# CircuitoEmitter2_0.net
KiCad netlist of a schematic drawn in EAGLE
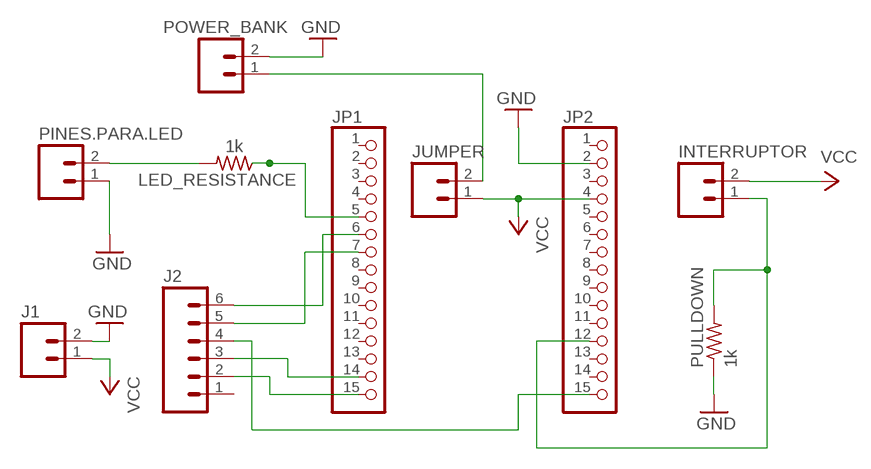
[diagram p0: schematic, sheet 1]

(export (version "E")
  (design (tool "Eeschema 10.0.6"))
  (components
    (comp (ref "INTERRUPTOR")
      (value "M02LOCK_LONGPADS")
      (footprint "eagle-import:1X02_LOCK_LONGPADS")
      (libsource (lib "eagle-import") (part "M02LOCK_LONGPADS"))
    )
    (comp (ref "J1")
      (value "M02LOCK_LONGPADS")
      (footprint "eagle-import:1X02_LOCK_LONGPADS")
      (libsource (lib "eagle-import") (part "M02LOCK_LONGPADS"))
    )
    (comp (ref "J2")
      (value "M06LONGPADS")
      (footprint "eagle-import:1X06_LONGPADS")
      (libsource (lib "eagle-import") (part "M06LONGPADS"))
    )
    (comp (ref "JP1")
      (value "PINHD-1X15")
      (footprint "eagle-import:1X15")
      (libsource (lib "eagle-import") (part "PINHD-1X15"))
    )
    (comp (ref "JP2")
      (value "PINHD-1X15")
      (footprint "eagle-import:1X15")
      (libsource (lib "eagle-import") (part "PINHD-1X15"))
    )
    (comp (ref "JUMPER")
      (value "M02LOCK_LONGPADS")
      (footprint "eagle-import:1X02_LOCK_LONGPADS")
      (libsource (lib "eagle-import") (part "M02LOCK_LONGPADS"))
    )
    (comp (ref "LED_RESISTANCE")
      (value "1k")
      (footprint "eagle-import:0204_7")
      (libsource (lib "eagle-import") (part "R-US_0204/7"))
    )
    (comp (ref "PINES.PARA.LED")
      (value "M02LOCK_LONGPADS")
      (footprint "eagle-import:1X02_LOCK_LONGPADS")
      (libsource (lib "eagle-import") (part "M02LOCK_LONGPADS"))
    )
    (comp (ref "POWER_BANK")
      (value "M02LOCK_LONGPADS")
      (footprint "eagle-import:1X02_LOCK_LONGPADS")
      (libsource (lib "eagle-import") (part "M02LOCK_LONGPADS"))
    )
    (comp (ref "PULLDOWN")
      (value "1k")
      (footprint "eagle-import:0204_7")
      (libsource (lib "eagle-import") (part "R-US_0204/7"))
    )
  )
  (nets
    (net (code "1") (name "GND") (class "Default")
      (node (ref "J1") (pin "2") (pinfunction "2_2") (pintype "passive"))
      (node (ref "JP2") (pin "2") (pinfunction "2_2") (pintype "passive"))
      (node (ref "PINES.PARA.LED") (pin "1") (pinfunction "1_1") (pintype "passive"))
      (node (ref "POWER_BANK") (pin "2") (pinfunction "2_2") (pintype "passive"))
      (node (ref "PULLDOWN") (pin "1") (pinfunction "1_1") (pintype "passive"))
    )
    (net (code "2") (name "Net-(INTERRUPTOR-Pad1)") (class "Default")
      (node (ref "INTERRUPTOR") (pin "1") (pinfunction "1_1") (pintype "passive"))
      (node (ref "JP2") (pin "12") (pinfunction "12_12") (pintype "passive"))
      (node (ref "PULLDOWN") (pin "2") (pinfunction "2_2") (pintype "passive"))
    )
    (net (code "3") (name "Net-(J2-Pad2)") (class "Default")
      (node (ref "J2") (pin "2") (pinfunction "2_2") (pintype "passive"))
      (node (ref "JP1") (pin "15") (pinfunction "15_15") (pintype "passive"))
    )
    (net (code "4") (name "Net-(J2-Pad3)") (class "Default")
      (node (ref "J2") (pin "3") (pinfunction "3_3") (pintype "passive"))
      (node (ref "JP1") (pin "14") (pinfunction "14_14") (pintype "passive"))
    )
    (net (code "5") (name "Net-(J2-Pad4)") (class "Default")
      (node (ref "J2") (pin "4") (pinfunction "4_4") (pintype "passive"))
      (node (ref "JP2") (pin "15") (pinfunction "15_15") (pintype "passive"))
    )
    (net (code "6") (name "Net-(J2-Pad5)") (class "Default")
      (node (ref "J2") (pin "5") (pinfunction "5_5") (pintype "passive"))
      (node (ref "JP1") (pin "7") (pinfunction "7_7") (pintype "passive"))
    )
    (net (code "7") (name "Net-(J2-Pad6)") (class "Default")
      (node (ref "J2") (pin "6") (pinfunction "6_6") (pintype "passive"))
      (node (ref "JP1") (pin "6") (pinfunction "6_6") (pintype "passive"))
    )
    (net (code "8") (name "Net-(JP1-Pad5)") (class "Default")
      (node (ref "JP1") (pin "5") (pinfunction "5_5") (pintype "passive"))
      (node (ref "LED_RESISTANCE") (pin "1") (pinfunction "1_1") (pintype "passive"))
    )
    (net (code "9") (name "Net-(JUMPER-Pad2)") (class "Default")
      (node (ref "JUMPER") (pin "2") (pinfunction "2_2") (pintype "passive"))
      (node (ref "POWER_BANK") (pin "1") (pinfunction "1_1") (pintype "passive"))
    )
    (net (code "10") (name "Net-(LED_RESISTANCE-Pad2)") (class "Default")
      (node (ref "LED_RESISTANCE") (pin "2") (pinfunction "2_2") (pintype "passive"))
      (node (ref "PINES.PARA.LED") (pin "2") (pinfunction "2_2") (pintype "passive"))
    )
    (net (code "11") (name "VCC") (class "Default")
      (node (ref "INTERRUPTOR") (pin "2") (pinfunction "2_2") (pintype "passive"))
      (node (ref "J1") (pin "1") (pinfunction "1_1") (pintype "passive"))
      (node (ref "JP2") (pin "4") (pinfunction "4_4") (pintype "passive"))
      (node (ref "JUMPER") (pin "1") (pinfunction "1_1") (pintype "passive"))
    )
    (net (code "12") (name "unconnected-(J2-Pad1)") (class "Default")
      (node (ref "J2") (pin "1") (pinfunction "1_1") (pintype "passive"))
    )
    (net (code "13") (name "unconnected-(JP1-Pad1)") (class "Default")
      (node (ref "JP1") (pin "1") (pinfunction "1_1") (pintype "passive"))
    )
    (net (code "14") (name "unconnected-(JP1-Pad2)") (class "Default")
      (node (ref "JP1") (pin "2") (pinfunction "2_2") (pintype "passive"))
    )
    (net (code "15") (name "unconnected-(JP1-Pad3)") (class "Default")
      (node (ref "JP1") (pin "3") (pinfunction "3_3") (pintype "passive"))
    )
    (net (code "16") (name "unconnected-(JP1-Pad4)") (class "Default")
      (node (ref "JP1") (pin "4") (pinfunction "4_4") (pintype "passive"))
    )
    (net (code "17") (name "unconnected-(JP1-Pad8)") (class "Default")
      (node (ref "JP1") (pin "8") (pinfunction "8_8") (pintype "passive"))
    )
    (net (code "18") (name "unconnected-(JP1-Pad9)") (class "Default")
      (node (ref "JP1") (pin "9") (pinfunction "9_9") (pintype "passive"))
    )
    (net (code "19") (name "unconnected-(JP1-Pad10)") (class "Default")
      (node (ref "JP1") (pin "10") (pinfunction "10_10") (pintype "passive"))
    )
    (net (code "20") (name "unconnected-(JP1-Pad11)") (class "Default")
      (node (ref "JP1") (pin "11") (pinfunction "11_11") (pintype "passive"))
    )
    (net (code "21") (name "unconnected-(JP1-Pad12)") (class "Default")
      (node (ref "JP1") (pin "12") (pinfunction "12_12") (pintype "passive"))
    )
    (net (code "22") (name "unconnected-(JP1-Pad13)") (class "Default")
      (node (ref "JP1") (pin "13") (pinfunction "13_13") (pintype "passive"))
    )
    (net (code "23") (name "unconnected-(JP2-Pad1)") (class "Default")
      (node (ref "JP2") (pin "1") (pinfunction "1_1") (pintype "passive"))
    )
    (net (code "24") (name "unconnected-(JP2-Pad3)") (class "Default")
      (node (ref "JP2") (pin "3") (pinfunction "3_3") (pintype "passive"))
    )
    (net (code "25") (name "unconnected-(JP2-Pad5)") (class "Default")
      (node (ref "JP2") (pin "5") (pinfunction "5_5") (pintype "passive"))
    )
    (net (code "26") (name "unconnected-(JP2-Pad6)") (class "Default")
      (node (ref "JP2") (pin "6") (pinfunction "6_6") (pintype "passive"))
    )
    (net (code "27") (name "unconnected-(JP2-Pad7)") (class "Default")
      (node (ref "JP2") (pin "7") (pinfunction "7_7") (pintype "passive"))
    )
    (net (code "28") (name "unconnected-(JP2-Pad8)") (class "Default")
      (node (ref "JP2") (pin "8") (pinfunction "8_8") (pintype "passive"))
    )
    (net (code "29") (name "unconnected-(JP2-Pad9)") (class "Default")
      (node (ref "JP2") (pin "9") (pinfunction "9_9") (pintype "passive"))
    )
    (net (code "30") (name "unconnected-(JP2-Pad10)") (class "Default")
      (node (ref "JP2") (pin "10") (pinfunction "10_10") (pintype "passive"))
    )
    (net (code "31") (name "unconnected-(JP2-Pad11)") (class "Default")
      (node (ref "JP2") (pin "11") (pinfunction "11_11") (pintype "passive"))
    )
    (net (code "32") (name "unconnected-(JP2-Pad13)") (class "Default")
      (node (ref "JP2") (pin "13") (pinfunction "13_13") (pintype "passive"))
    )
    (net (code "33") (name "unconnected-(JP2-Pad14)") (class "Default")
      (node (ref "JP2") (pin "14") (pinfunction "14_14") (pintype "passive"))
    )
  )
)
